# micro.net
KiCad netlist of a schematic drawn in Altium Designer
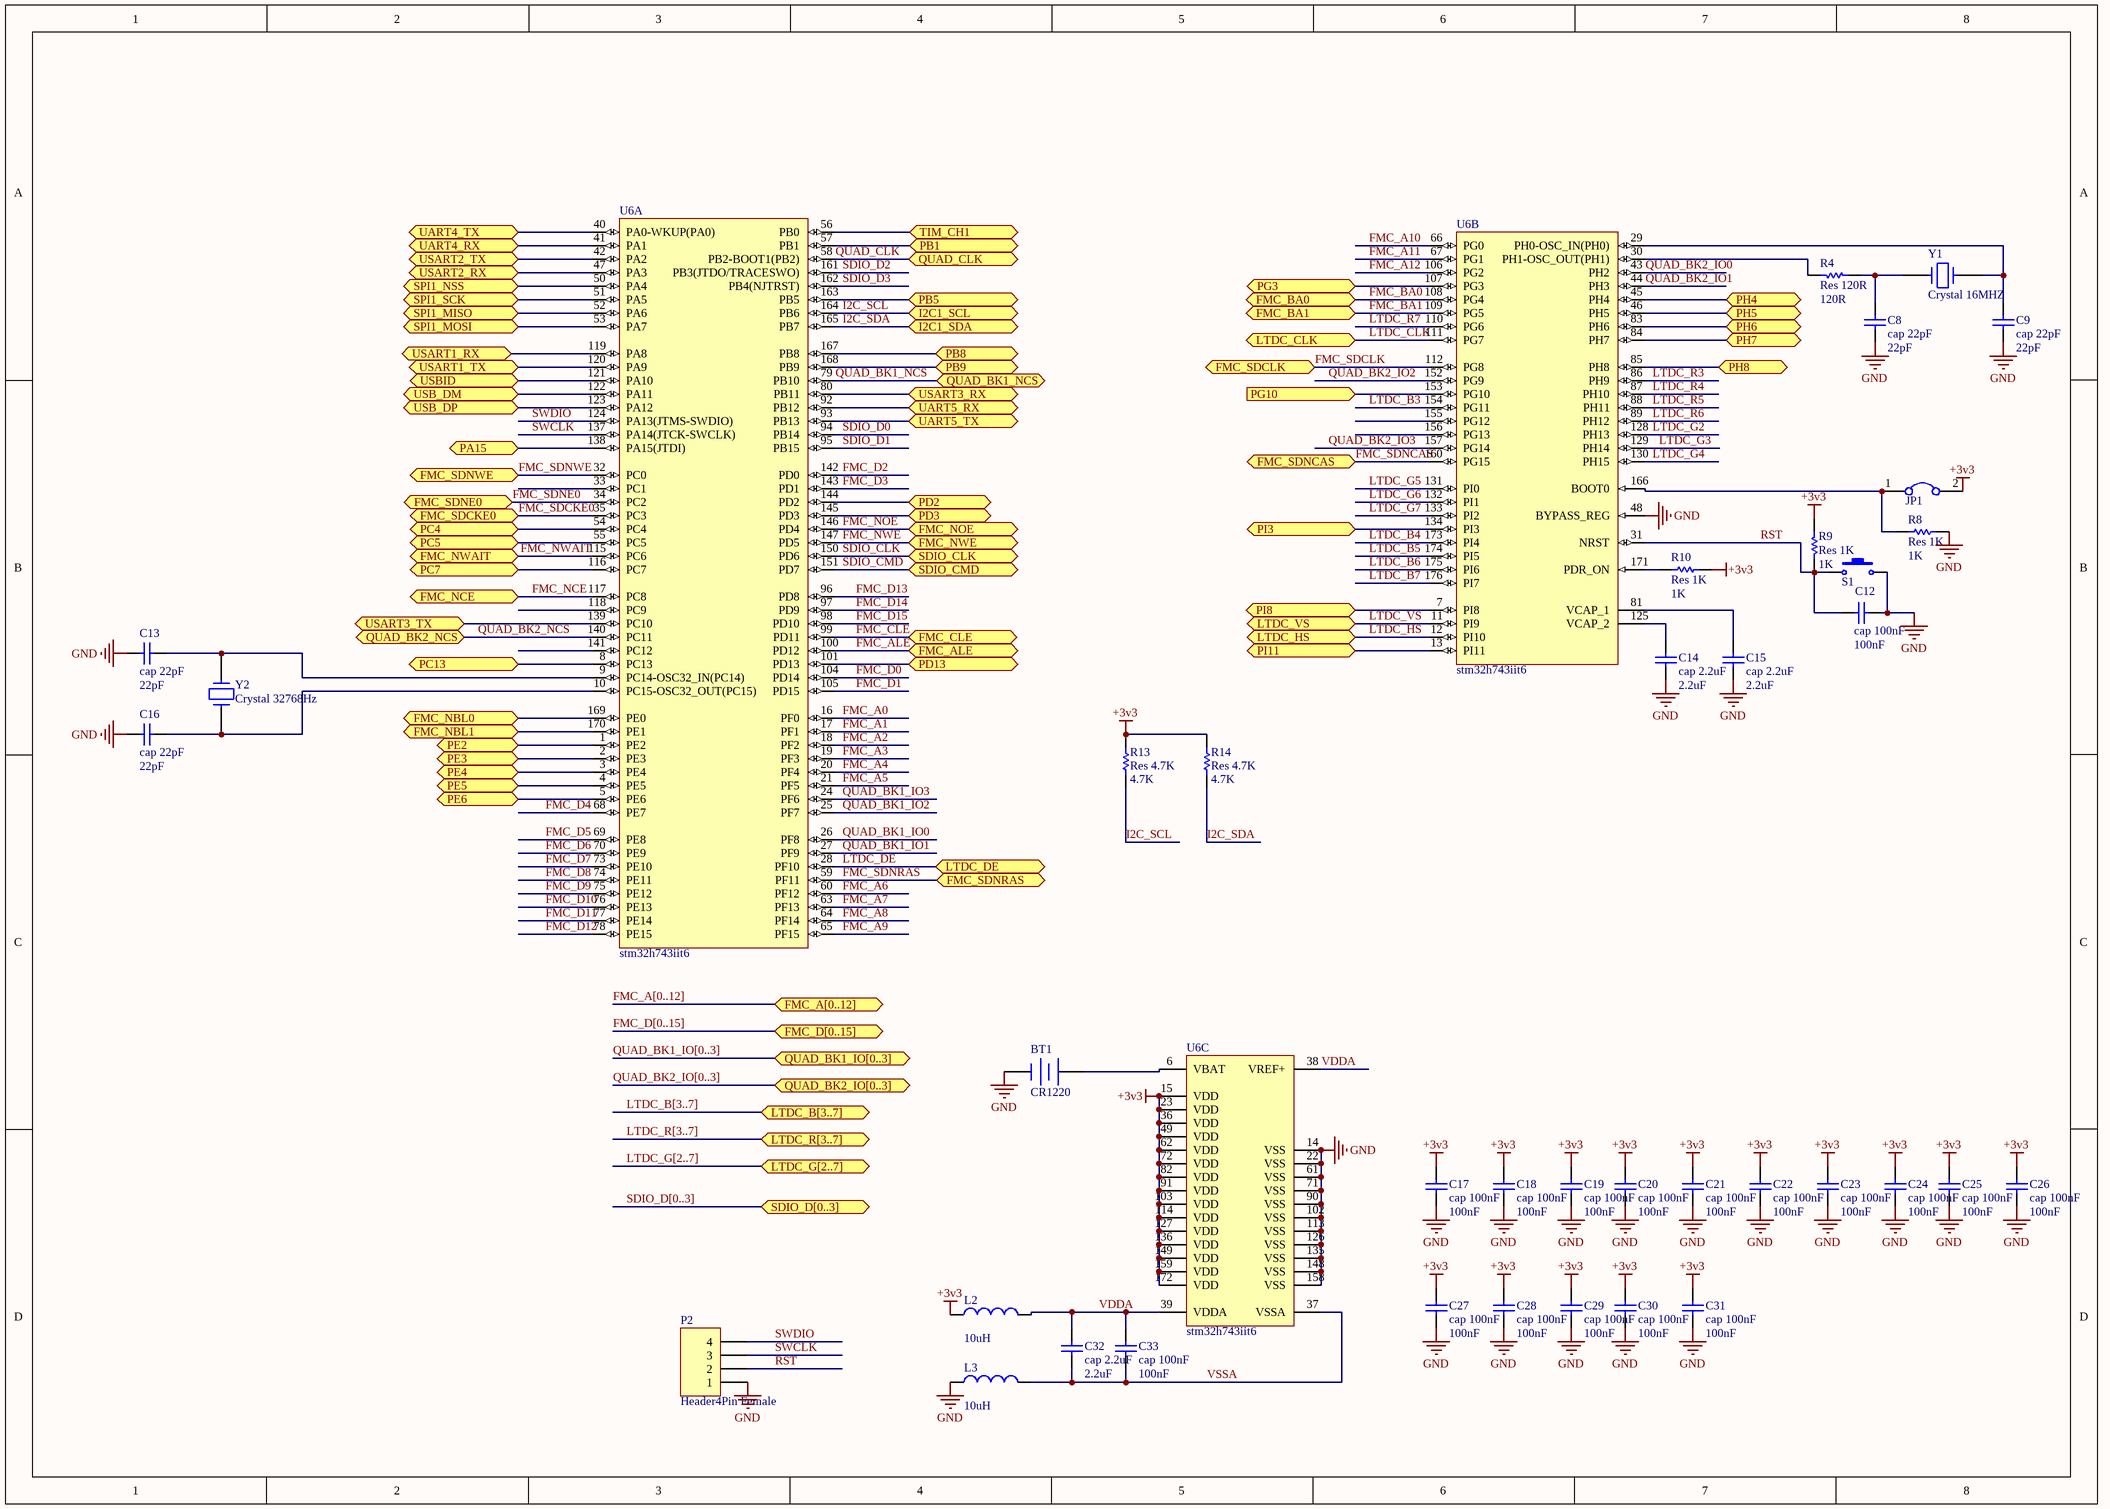
[diagram p0: micro.SchDoc]

(export (version "E")
  (design (tool "Eeschema 10.0.6"))
  (components
    (comp (ref "BT1")
      (value "CR1220")
      (footprint "BTH1220")
      (description "CoinCell Battery")
      (fields (field (name "PUBLISHER") "Altium Limited"))
      (libsource (lib "Miscellaneous Devices") (part "Battery"))
    )
    (comp (ref "C8")
      (value "cap 22pF")
      (footprint "Cap 805")
      (description "Capacitor")
      (fields (field (name "ALTIUM_VALUE") "22pF") (field (name "PUBLISHER") "Altium Limited"))
      (libsource (lib "Miscellaneous Devices") (part "Cap"))
    )
    (comp (ref "C9")
      (value "cap 22pF")
      (footprint "Cap 805")
      (description "Capacitor")
      (fields (field (name "ALTIUM_VALUE") "22pF") (field (name "PUBLISHER") "Altium Limited"))
      (libsource (lib "Miscellaneous Devices") (part "Cap"))
    )
    (comp (ref "C12")
      (value "cap 100nF")
      (footprint "Cap 805")
      (description "Capacitor")
      (fields (field (name "ALTIUM_VALUE") "100nF") (field (name "PUBLISHER") "Altium Limited"))
      (libsource (lib "Miscellaneous Devices") (part "Cap"))
    )
    (comp (ref "C13")
      (value "cap 22pF")
      (footprint "Cap 805")
      (description "Capacitor")
      (fields (field (name "ALTIUM_VALUE") "22pF") (field (name "PUBLISHER") "Altium Limited"))
      (libsource (lib "Miscellaneous Devices") (part "Cap"))
    )
    (comp (ref "C14")
      (value "cap 2.2uF")
      (footprint "Cap 805")
      (description "Capacitor")
      (fields (field (name "ALTIUM_VALUE") "2.2uF") (field (name "PUBLISHER") "Altium Limited"))
      (libsource (lib "Miscellaneous Devices") (part "Cap"))
    )
    (comp (ref "C15")
      (value "cap 2.2uF")
      (footprint "Cap 805")
      (description "Capacitor")
      (fields (field (name "ALTIUM_VALUE") "2.2uF") (field (name "PUBLISHER") "Altium Limited"))
      (libsource (lib "Miscellaneous Devices") (part "Cap"))
    )
    (comp (ref "C16")
      (value "cap 22pF")
      (footprint "Cap 805")
      (description "Capacitor")
      (fields (field (name "ALTIUM_VALUE") "22pF") (field (name "PUBLISHER") "Altium Limited"))
      (libsource (lib "Miscellaneous Devices") (part "Cap"))
    )
    (comp (ref "C17")
      (value "cap 100nF")
      (footprint "Cap 805")
      (description "Capacitor")
      (fields (field (name "ALTIUM_VALUE") "100nF") (field (name "PUBLISHER") "Altium Limited"))
      (libsource (lib "Miscellaneous Devices") (part "Cap"))
    )
    (comp (ref "C18")
      (value "cap 100nF")
      (footprint "Cap 805")
      (description "Capacitor")
      (fields (field (name "ALTIUM_VALUE") "100nF") (field (name "PUBLISHER") "Altium Limited"))
      (libsource (lib "Miscellaneous Devices") (part "Cap"))
    )
    (comp (ref "C19")
      (value "cap 100nF")
      (footprint "Cap 805")
      (description "Capacitor")
      (fields (field (name "ALTIUM_VALUE") "100nF") (field (name "PUBLISHER") "Altium Limited"))
      (libsource (lib "Miscellaneous Devices") (part "Cap"))
    )
    (comp (ref "C20")
      (value "cap 100nF")
      (footprint "Cap 805")
      (description "Capacitor")
      (fields (field (name "ALTIUM_VALUE") "100nF") (field (name "PUBLISHER") "Altium Limited"))
      (libsource (lib "Miscellaneous Devices") (part "Cap"))
    )
    (comp (ref "C21")
      (value "cap 100nF")
      (footprint "Cap 805")
      (description "Capacitor")
      (fields (field (name "ALTIUM_VALUE") "100nF") (field (name "PUBLISHER") "Altium Limited"))
      (libsource (lib "Miscellaneous Devices") (part "Cap"))
    )
    (comp (ref "C22")
      (value "cap 100nF")
      (footprint "Cap 805")
      (description "Capacitor")
      (fields (field (name "ALTIUM_VALUE") "100nF") (field (name "PUBLISHER") "Altium Limited"))
      (libsource (lib "Miscellaneous Devices") (part "Cap"))
    )
    (comp (ref "C23")
      (value "cap 100nF")
      (footprint "Cap 805")
      (description "Capacitor")
      (fields (field (name "ALTIUM_VALUE") "100nF") (field (name "PUBLISHER") "Altium Limited"))
      (libsource (lib "Miscellaneous Devices") (part "Cap"))
    )
    (comp (ref "C24")
      (value "cap 100nF")
      (footprint "Cap 805")
      (description "Capacitor")
      (fields (field (name "ALTIUM_VALUE") "100nF") (field (name "PUBLISHER") "Altium Limited"))
      (libsource (lib "Miscellaneous Devices") (part "Cap"))
    )
    (comp (ref "C25")
      (value "cap 100nF")
      (footprint "Cap 805")
      (description "Capacitor")
      (fields (field (name "ALTIUM_VALUE") "100nF") (field (name "PUBLISHER") "Altium Limited"))
      (libsource (lib "Miscellaneous Devices") (part "Cap"))
    )
    (comp (ref "C26")
      (value "cap 100nF")
      (footprint "Cap 805")
      (description "Capacitor")
      (fields (field (name "ALTIUM_VALUE") "100nF") (field (name "PUBLISHER") "Altium Limited"))
      (libsource (lib "Miscellaneous Devices") (part "Cap"))
    )
    (comp (ref "C27")
      (value "cap 100nF")
      (footprint "Cap 805")
      (description "Capacitor")
      (fields (field (name "ALTIUM_VALUE") "100nF") (field (name "PUBLISHER") "Altium Limited"))
      (libsource (lib "Miscellaneous Devices") (part "Cap"))
    )
    (comp (ref "C28")
      (value "cap 100nF")
      (footprint "Cap 805")
      (description "Capacitor")
      (fields (field (name "ALTIUM_VALUE") "100nF") (field (name "PUBLISHER") "Altium Limited"))
      (libsource (lib "Miscellaneous Devices") (part "Cap"))
    )
    (comp (ref "C29")
      (value "cap 100nF")
      (footprint "Cap 805")
      (description "Capacitor")
      (fields (field (name "ALTIUM_VALUE") "100nF") (field (name "PUBLISHER") "Altium Limited"))
      (libsource (lib "Miscellaneous Devices") (part "Cap"))
    )
    (comp (ref "C30")
      (value "cap 100nF")
      (footprint "Cap 805")
      (description "Capacitor")
      (fields (field (name "ALTIUM_VALUE") "100nF") (field (name "PUBLISHER") "Altium Limited"))
      (libsource (lib "Miscellaneous Devices") (part "Cap"))
    )
    (comp (ref "C31")
      (value "cap 100nF")
      (footprint "Cap 805")
      (description "Capacitor")
      (fields (field (name "ALTIUM_VALUE") "100nF") (field (name "PUBLISHER") "Altium Limited"))
      (libsource (lib "Miscellaneous Devices") (part "Cap"))
    )
    (comp (ref "C32")
      (value "cap 2.2uF")
      (footprint "Cap 805")
      (description "Capacitor")
      (fields (field (name "ALTIUM_VALUE") "2.2uF") (field (name "PUBLISHER") "Altium Limited"))
      (libsource (lib "Miscellaneous Devices") (part "Cap"))
    )
    (comp (ref "C33")
      (value "cap 100nF")
      (footprint "Cap 805")
      (description "Capacitor")
      (fields (field (name "ALTIUM_VALUE") "100nF") (field (name "PUBLISHER") "Altium Limited"))
      (libsource (lib "Miscellaneous Devices") (part "Cap"))
    )
    (comp (ref "JP1")
      (value "Jumper")
      (footprint "Jumper Small - 2.54 - GRAY")
      (description "Boot select")
      (libsource (lib "Altium (2)") (part "Jumper"))
    )
    (comp (ref "L2")
      (value "10uH")
      (footprint "IND1206")
      (description "Inductor")
      (fields (field (name "Comment") "inductor 10uH") (field (name "PUBLISHER") "Altium Limited"))
      (libsource (lib "Miscellaneous Devices") (part "Inductor"))
    )
    (comp (ref "L3")
      (value "10uH")
      (footprint "IND1206")
      (description "Inductor")
      (fields (field (name "Comment") "inductor 10uH") (field (name "PUBLISHER") "Altium Limited"))
      (libsource (lib "Miscellaneous Devices") (part "Inductor"))
    )
    (comp (ref "P2")
      (value "Header4Pin Female")
      (footprint "HDR1X4")
      (description "Header, 4-Pin")
      (fields (field (name "PUBLISHER") "Altium Limited"))
      (libsource (lib "Miscellaneous Connectors") (part "Header 4"))
    )
    (comp (ref "R4")
      (value "Res 120R")
      (footprint "RES 0805 (2012X06L)")
      (description "Resistor")
      (fields (field (name "ALTIUM_VALUE") "120R") (field (name "PUBLISHER") "Altium Limited"))
      (libsource (lib "Miscellaneous Devices") (part "Res1"))
    )
    (comp (ref "R8")
      (value "Res 1K")
      (footprint "RES 0805 (2012X06L)")
      (description "Resistor")
      (fields (field (name "ALTIUM_VALUE") "1K") (field (name "PUBLISHER") "Altium Limited"))
      (libsource (lib "Miscellaneous Devices") (part "Res1"))
    )
    (comp (ref "R9")
      (value "Res 1K")
      (footprint "RES 0805 (2012X06L)")
      (description "Resistor")
      (fields (field (name "ALTIUM_VALUE") "1K") (field (name "PUBLISHER") "Altium Limited"))
      (libsource (lib "Miscellaneous Devices") (part "Res1"))
    )
    (comp (ref "R10")
      (value "Res 1K")
      (footprint "RES 0805 (2012X06L)")
      (description "Resistor")
      (fields (field (name "ALTIUM_VALUE") "1K") (field (name "PUBLISHER") "Altium Limited"))
      (libsource (lib "Miscellaneous Devices") (part "Res1"))
    )
    (comp (ref "R13")
      (value "Res 4.7K")
      (footprint "RES 0805 (2012X06L)")
      (description "Resistor")
      (fields (field (name "ALTIUM_VALUE") "4.7K") (field (name "PUBLISHER") "Altium Limited"))
      (libsource (lib "Miscellaneous Devices") (part "Res1"))
    )
    (comp (ref "R14")
      (value "Res 4.7K")
      (footprint "RES 0805 (2012X06L)")
      (description "Resistor")
      (fields (field (name "ALTIUM_VALUE") "4.7K") (field (name "PUBLISHER") "Altium Limited"))
      (libsource (lib "Miscellaneous Devices") (part "Res1"))
    )
    (comp (ref "S1")
      (value "Switch PB")
      (footprint "Switch - Push to On")
      (description "Push Button Switch")
      (libsource (lib "Altium (2)") (part "Switch PB"))
    )
    (comp (ref "U6")
      (value "stm32h743iit6")
      (footprint "STM-LQFP176_M")
      (fields (field (name "MANUFACTURER") "STMicroelectronics") (field (name "PARTNUMBER") "STM32F429IGT6"))
      (libsource (lib "STMicroelectronics STM32 F4") (part "STM32F429IGT6"))
    )
    (comp (ref "Y1")
      (value "Crystal 16MHZ")
      (footprint "CRYSTAL Small")
      (description "Crystal")
      (libsource (lib "Altium library (www.AVRelec.com)") (part "CRYSTAL"))
    )
    (comp (ref "Y2")
      (value "Crystal 32768Hz")
      (footprint "XTAL RTC")
      (description "Crystal")
      (libsource (lib "Altium library (www.AVRelec.com)") (part "CRYSTAL"))
    )
  )
  (nets
    (net (code "1") (name "+3v3") (class "Default")
      (node (ref "C17") (pin "2") (pinfunction "2_2") (pintype "passive"))
      (node (ref "C18") (pin "2") (pinfunction "2_2") (pintype "passive"))
      (node (ref "C19") (pin "2") (pinfunction "2_2") (pintype "passive"))
      (node (ref "C20") (pin "2") (pinfunction "2_2") (pintype "passive"))
      (node (ref "C21") (pin "2") (pinfunction "2_2") (pintype "passive"))
      (node (ref "C22") (pin "2") (pinfunction "2_2") (pintype "passive"))
      (node (ref "C23") (pin "2") (pinfunction "2_2") (pintype "passive"))
      (node (ref "C24") (pin "2") (pinfunction "2_2") (pintype "passive"))
      (node (ref "C25") (pin "2") (pinfunction "2_2") (pintype "passive"))
      (node (ref "C26") (pin "2") (pinfunction "2_2") (pintype "passive"))
      (node (ref "C27") (pin "2") (pinfunction "2_2") (pintype "passive"))
      (node (ref "C28") (pin "2") (pinfunction "2_2") (pintype "passive"))
      (node (ref "C29") (pin "2") (pinfunction "2_2") (pintype "passive"))
      (node (ref "C30") (pin "2") (pinfunction "2_2") (pintype "passive"))
      (node (ref "C31") (pin "2") (pinfunction "2_2") (pintype "passive"))
      (node (ref "JP1") (pin "2") (pinfunction "2_2") (pintype "passive"))
      (node (ref "L2") (pin "1") (pinfunction "1_1") (pintype "passive"))
      (node (ref "R10") (pin "2") (pinfunction "2_2") (pintype "passive"))
      (node (ref "R13") (pin "1") (pinfunction "1_1") (pintype "passive"))
      (node (ref "R14") (pin "1") (pinfunction "1_1") (pintype "passive"))
      (node (ref "R9") (pin "1") (pinfunction "1_1") (pintype "passive"))
      (node (ref "U6") (pin "103") (pinfunction "VDD_103") (pintype "power_in"))
      (node (ref "U6") (pin "114") (pinfunction "VDD_114") (pintype "power_in"))
      (node (ref "U6") (pin "127") (pinfunction "VDD_127") (pintype "power_in"))
      (node (ref "U6") (pin "136") (pinfunction "VDD_136") (pintype "power_in"))
      (node (ref "U6") (pin "149") (pinfunction "VDD_149") (pintype "power_in"))
      (node (ref "U6") (pin "15") (pinfunction "VDD_15") (pintype "power_in"))
      (node (ref "U6") (pin "159") (pinfunction "VDD_159") (pintype "power_in"))
      (node (ref "U6") (pin "172") (pinfunction "VDD_172") (pintype "power_in"))
      (node (ref "U6") (pin "23") (pinfunction "VDD_23") (pintype "power_in"))
      (node (ref "U6") (pin "36") (pinfunction "VDD_36") (pintype "power_in"))
      (node (ref "U6") (pin "49") (pinfunction "VDD_49") (pintype "power_in"))
      (node (ref "U6") (pin "62") (pinfunction "VDD_62") (pintype "power_in"))
      (node (ref "U6") (pin "72") (pinfunction "VDD_72") (pintype "power_in"))
      (node (ref "U6") (pin "82") (pinfunction "VDD_82") (pintype "power_in"))
      (node (ref "U6") (pin "91") (pinfunction "VDD_91") (pintype "power_in"))
    )
    (net (code "2") (name "/FMC_A0") (class "Default")
      (node (ref "U6") (pin "16") (pinfunction "PF0_16") (pintype "bidirectional"))
    )
    (net (code "3") (name "/FMC_A1") (class "Default")
      (node (ref "U6") (pin "17") (pinfunction "PF1_17") (pintype "bidirectional"))
    )
    (net (code "4") (name "/FMC_A2") (class "Default")
      (node (ref "U6") (pin "18") (pinfunction "PF2_18") (pintype "bidirectional"))
    )
    (net (code "5") (name "/FMC_A3") (class "Default")
      (node (ref "U6") (pin "19") (pinfunction "PF3_19") (pintype "bidirectional"))
    )
    (net (code "6") (name "/FMC_A4") (class "Default")
      (node (ref "U6") (pin "20") (pinfunction "PF4_20") (pintype "bidirectional"))
    )
    (net (code "7") (name "/FMC_A5") (class "Default")
      (node (ref "U6") (pin "21") (pinfunction "PF5_21") (pintype "bidirectional"))
    )
    (net (code "8") (name "/FMC_A6") (class "Default")
      (node (ref "U6") (pin "60") (pinfunction "PF12_60") (pintype "bidirectional"))
    )
    (net (code "9") (name "/FMC_A7") (class "Default")
      (node (ref "U6") (pin "63") (pinfunction "PF13_63") (pintype "bidirectional"))
    )
    (net (code "10") (name "/FMC_A8") (class "Default")
      (node (ref "U6") (pin "64") (pinfunction "PF14_64") (pintype "bidirectional"))
    )
    (net (code "11") (name "/FMC_A9") (class "Default")
      (node (ref "U6") (pin "65") (pinfunction "PF15_65") (pintype "bidirectional"))
    )
    (net (code "12") (name "/FMC_A10") (class "Default")
      (node (ref "U6") (pin "66") (pinfunction "PG0_66") (pintype "bidirectional"))
    )
    (net (code "13") (name "/FMC_A11") (class "Default")
      (node (ref "U6") (pin "67") (pinfunction "PG1_67") (pintype "bidirectional"))
    )
    (net (code "14") (name "/FMC_A12") (class "Default")
      (node (ref "U6") (pin "106") (pinfunction "PG2_106") (pintype "bidirectional"))
    )
    (net (code "15") (name "/FMC_ALE") (class "Default")
      (node (ref "U6") (pin "100") (pinfunction "PD12_100") (pintype "bidirectional"))
    )
    (net (code "17") (name "/FMC_BA0") (class "Default")
      (node (ref "U6") (pin "108") (pinfunction "PG4_108") (pintype "bidirectional"))
    )
    (net (code "18") (name "/FMC_BA1") (class "Default")
      (node (ref "U6") (pin "109") (pinfunction "PG5_109") (pintype "bidirectional"))
    )
    (net (code "19") (name "/FMC_CLE") (class "Default")
      (node (ref "U6") (pin "99") (pinfunction "PD11_99") (pintype "bidirectional"))
    )
    (net (code "20") (name "/FMC_D0") (class "Default")
      (node (ref "U6") (pin "104") (pinfunction "PD14_104") (pintype "bidirectional"))
    )
    (net (code "21") (name "/FMC_D1") (class "Default")
      (node (ref "U6") (pin "105") (pinfunction "PD15_105") (pintype "bidirectional"))
    )
    (net (code "22") (name "/FMC_D2") (class "Default")
      (node (ref "U6") (pin "142") (pinfunction "PD0_142") (pintype "bidirectional"))
    )
    (net (code "23") (name "/FMC_D3") (class "Default")
      (node (ref "U6") (pin "143") (pinfunction "PD1_143") (pintype "bidirectional"))
    )
    (net (code "24") (name "/FMC_D4") (class "Default")
      (node (ref "U6") (pin "68") (pinfunction "PE7_68") (pintype "bidirectional"))
    )
    (net (code "25") (name "/FMC_D5") (class "Default")
      (node (ref "U6") (pin "69") (pinfunction "PE8_69") (pintype "bidirectional"))
    )
    (net (code "26") (name "/FMC_D6") (class "Default")
      (node (ref "U6") (pin "70") (pinfunction "PE9_70") (pintype "bidirectional"))
    )
    (net (code "27") (name "/FMC_D7") (class "Default")
      (node (ref "U6") (pin "73") (pinfunction "PE10_73") (pintype "bidirectional"))
    )
    (net (code "28") (name "/FMC_D8") (class "Default")
      (node (ref "U6") (pin "74") (pinfunction "PE11_74") (pintype "bidirectional"))
    )
    (net (code "29") (name "/FMC_D9") (class "Default")
      (node (ref "U6") (pin "75") (pinfunction "PE12_75") (pintype "bidirectional"))
    )
    (net (code "30") (name "/FMC_D10") (class "Default")
      (node (ref "U6") (pin "76") (pinfunction "PE13_76") (pintype "bidirectional"))
    )
    (net (code "31") (name "/FMC_D11") (class "Default")
      (node (ref "U6") (pin "77") (pinfunction "PE14_77") (pintype "bidirectional"))
    )
    (net (code "32") (name "/FMC_D12") (class "Default")
      (node (ref "U6") (pin "78") (pinfunction "PE15_78") (pintype "bidirectional"))
    )
    (net (code "33") (name "/FMC_D13") (class "Default")
      (node (ref "U6") (pin "96") (pinfunction "PD8_96") (pintype "bidirectional"))
    )
    (net (code "34") (name "/FMC_D14") (class "Default")
      (node (ref "U6") (pin "97") (pinfunction "PD9_97") (pintype "bidirectional"))
    )
    (net (code "35") (name "/FMC_D15") (class "Default")
      (node (ref "U6") (pin "98") (pinfunction "PD10_98") (pintype "bidirectional"))
    )
    (net (code "37") (name "/FMC_NBL0") (class "Default")
      (node (ref "U6") (pin "169") (pinfunction "PE0_169") (pintype "bidirectional"))
    )
    (net (code "38") (name "/FMC_NBL1") (class "Default")
      (node (ref "U6") (pin "170") (pinfunction "PE1_170") (pintype "bidirectional"))
    )
    (net (code "39") (name "/FMC_NCE") (class "Default")
      (node (ref "U6") (pin "117") (pinfunction "PC8_117") (pintype "bidirectional"))
    )
    (net (code "40") (name "/FMC_NOE") (class "Default")
      (node (ref "U6") (pin "146") (pinfunction "PD4_146") (pintype "bidirectional"))
    )
    (net (code "41") (name "/FMC_NWAIT") (class "Default")
      (node (ref "U6") (pin "115") (pinfunction "PC6_115") (pintype "bidirectional"))
    )
    (net (code "42") (name "/FMC_NWE") (class "Default")
      (node (ref "U6") (pin "147") (pinfunction "PD5_147") (pintype "bidirectional"))
    )
    (net (code "43") (name "/FMC_SDCKE0") (class "Default")
      (node (ref "U6") (pin "35") (pinfunction "PC3_35") (pintype "bidirectional"))
    )
    (net (code "44") (name "/FMC_SDCLK") (class "Default")
      (node (ref "U6") (pin "112") (pinfunction "PG8_112") (pintype "bidirectional"))
    )
    (net (code "45") (name "/FMC_SDNCAS") (class "Default")
      (node (ref "U6") (pin "160") (pinfunction "PG15_160") (pintype "bidirectional"))
    )
    (net (code "46") (name "/FMC_SDNE0") (class "Default")
      (node (ref "U6") (pin "34") (pinfunction "PC2_34") (pintype "bidirectional"))
    )
    (net (code "47") (name "/FMC_SDNRAS") (class "Default")
      (node (ref "U6") (pin "59") (pinfunction "PF11_59") (pintype "bidirectional"))
    )
    (net (code "48") (name "/FMC_SDNWE") (class "Default")
      (node (ref "U6") (pin "32") (pinfunction "PC0_32") (pintype "bidirectional"))
    )
    (net (code "49") (name "/I2C_SCL") (class "Default")
      (node (ref "R13") (pin "2") (pinfunction "2_2") (pintype "passive"))
      (node (ref "U6") (pin "164") (pinfunction "PB6_164") (pintype "bidirectional"))
    )
    (net (code "50") (name "/I2C_SDA") (class "Default")
      (node (ref "R14") (pin "2") (pinfunction "2_2") (pintype "passive"))
      (node (ref "U6") (pin "165") (pinfunction "PB7_165") (pintype "bidirectional"))
    )
    (net (code "51") (name "/LTDC_B3") (class "Default")
      (node (ref "U6") (pin "154") (pinfunction "PG11_154") (pintype "bidirectional"))
    )
    (net (code "52") (name "/LTDC_B4") (class "Default")
      (node (ref "U6") (pin "173") (pinfunction "PI4_173") (pintype "bidirectional"))
    )
    (net (code "53") (name "/LTDC_B5") (class "Default")
      (node (ref "U6") (pin "174") (pinfunction "PI5_174") (pintype "bidirectional"))
    )
    (net (code "54") (name "/LTDC_B6") (class "Default")
      (node (ref "U6") (pin "175") (pinfunction "PI6_175") (pintype "bidirectional"))
    )
    (net (code "55") (name "/LTDC_B7") (class "Default")
      (node (ref "U6") (pin "176") (pinfunction "PI7_176") (pintype "bidirectional"))
    )
    (net (code "57") (name "/LTDC_CLK") (class "Default")
      (node (ref "U6") (pin "111") (pinfunction "PG7_111") (pintype "bidirectional"))
    )
    (net (code "58") (name "/LTDC_DE") (class "Default")
      (node (ref "U6") (pin "28") (pinfunction "PF10_28") (pintype "bidirectional"))
    )
    (net (code "59") (name "/LTDC_G2") (class "Default")
      (node (ref "U6") (pin "128") (pinfunction "PH13_128") (pintype "bidirectional"))
    )
    (net (code "60") (name "/LTDC_G3") (class "Default")
      (node (ref "U6") (pin "129") (pinfunction "PH14_129") (pintype "bidirectional"))
    )
    (net (code "61") (name "/LTDC_G4") (class "Default")
      (node (ref "U6") (pin "130") (pinfunction "PH15_130") (pintype "bidirectional"))
    )
    (net (code "62") (name "/LTDC_G5") (class "Default")
      (node (ref "U6") (pin "131") (pinfunction "PI0_131") (pintype "bidirectional"))
    )
    (net (code "63") (name "/LTDC_G6") (class "Default")
      (node (ref "U6") (pin "132") (pinfunction "PI1_132") (pintype "bidirectional"))
    )
    (net (code "64") (name "/LTDC_G7") (class "Default")
      (node (ref "U6") (pin "133") (pinfunction "PI2_133") (pintype "bidirectional"))
    )
    (net (code "66") (name "/LTDC_HS") (class "Default")
      (node (ref "U6") (pin "12") (pinfunction "PI10_12") (pintype "bidirectional"))
    )
    (net (code "67") (name "/LTDC_R3") (class "Default")
      (node (ref "U6") (pin "86") (pinfunction "PH9_86") (pintype "bidirectional"))
    )
    (net (code "68") (name "/LTDC_R4") (class "Default")
      (node (ref "U6") (pin "87") (pinfunction "PH10_87") (pintype "bidirectional"))
    )
    (net (code "69") (name "/LTDC_R5") (class "Default")
      (node (ref "U6") (pin "88") (pinfunction "PH11_88") (pintype "bidirectional"))
    )
    (net (code "70") (name "/LTDC_R6") (class "Default")
      (node (ref "U6") (pin "89") (pinfunction "PH12_89") (pintype "bidirectional"))
    )
    (net (code "71") (name "/LTDC_R7") (class "Default")
      (node (ref "U6") (pin "110") (pinfunction "PG6_110") (pintype "bidirectional"))
    )
    (net (code "73") (name "/LTDC_VS") (class "Default")
      (node (ref "U6") (pin "11") (pinfunction "PI9_11") (pintype "bidirectional"))
    )
    (net (code "74") (name "/PA15") (class "Default")
      (node (ref "U6") (pin "138") (pinfunction "PA15(JTDI)_138") (pintype "bidirectional"))
    )
    (net (code "75") (name "/PB1") (class "Default")
      (node (ref "U6") (pin "57") (pinfunction "PB1_57") (pintype "bidirectional"))
    )
    (net (code "76") (name "/PB5") (class "Default")
      (node (ref "U6") (pin "163") (pinfunction "PB5_163") (pintype "bidirectional"))
    )
    (net (code "77") (name "/PB8") (class "Default")
      (node (ref "U6") (pin "167") (pinfunction "PB8_167") (pintype "bidirectional"))
    )
    (net (code "78") (name "/PB9") (class "Default")
      (node (ref "U6") (pin "168") (pinfunction "PB9_168") (pintype "bidirectional"))
    )
    (net (code "79") (name "/PC4") (class "Default")
      (node (ref "U6") (pin "54") (pinfunction "PC4_54") (pintype "bidirectional"))
    )
    (net (code "80") (name "/PC5") (class "Default")
      (node (ref "U6") (pin "55") (pinfunction "PC5_55") (pintype "bidirectional"))
    )
    (net (code "81") (name "/PC7") (class "Default")
      (node (ref "U6") (pin "116") (pinfunction "PC7_116") (pintype "bidirectional"))
    )
    (net (code "82") (name "/PC13") (class "Default")
      (node (ref "U6") (pin "8") (pinfunction "PC13_8") (pintype "bidirectional"))
    )
    (net (code "83") (name "/PD2") (class "Default")
      (node (ref "U6") (pin "144") (pinfunction "PD2_144") (pintype "bidirectional"))
    )
    (net (code "84") (name "/PD3") (class "Default")
      (node (ref "U6") (pin "145") (pinfunction "PD3_145") (pintype "bidirectional"))
    )
    (net (code "85") (name "/PD13") (class "Default")
      (node (ref "U6") (pin "101") (pinfunction "PD13_101") (pintype "bidirectional"))
    )
    (net (code "86") (name "/PE2") (class "Default")
      (node (ref "U6") (pin "1") (pinfunction "PE2_1") (pintype "bidirectional"))
    )
    (net (code "87") (name "/PE3") (class "Default")
      (node (ref "U6") (pin "2") (pinfunction "PE3_2") (pintype "bidirectional"))
    )
    (net (code "88") (name "/PE4") (class "Default")
      (node (ref "U6") (pin "3") (pinfunction "PE4_3") (pintype "bidirectional"))
    )
    (net (code "89") (name "/PE5") (class "Default")
      (node (ref "U6") (pin "4") (pinfunction "PE5_4") (pintype "bidirectional"))
    )
    (net (code "90") (name "/PE6") (class "Default")
      (node (ref "U6") (pin "5") (pinfunction "PE6_5") (pintype "bidirectional"))
    )
    (net (code "91") (name "/PG3") (class "Default")
      (node (ref "U6") (pin "107") (pinfunction "PG3_107") (pintype "bidirectional"))
    )
    (net (code "92") (name "/PG10") (class "Default")
      (node (ref "U6") (pin "153") (pinfunction "PG10_153") (pintype "bidirectional"))
    )
    (net (code "93") (name "/PH4") (class "Default")
      (node (ref "U6") (pin "45") (pinfunction "PH4_45") (pintype "bidirectional"))
    )
    (net (code "94") (name "/PH5") (class "Default")
      (node (ref "U6") (pin "46") (pinfunction "PH5_46") (pintype "bidirectional"))
    )
    (net (code "95") (name "/PH6") (class "Default")
      (node (ref "U6") (pin "83") (pinfunction "PH6_83") (pintype "bidirectional"))
    )
    (net (code "96") (name "/PH7") (class "Default")
      (node (ref "U6") (pin "84") (pinfunction "PH7_84") (pintype "bidirectional"))
    )
    (net (code "97") (name "/PH8") (class "Default")
      (node (ref "U6") (pin "85") (pinfunction "PH8_85") (pintype "bidirectional"))
    )
    (net (code "98") (name "/PI3") (class "Default")
      (node (ref "U6") (pin "134") (pinfunction "PI3_134") (pintype "bidirectional"))
    )
    (net (code "99") (name "/PI8") (class "Default")
      (node (ref "U6") (pin "7") (pinfunction "PI8_7") (pintype "bidirectional"))
    )
    (net (code "100") (name "/PI11") (class "Default")
      (node (ref "U6") (pin "13") (pinfunction "PI11_13") (pintype "bidirectional"))
    )
    (net (code "101") (name "/QUAD_BK1_IO0") (class "Default")
      (node (ref "U6") (pin "26") (pinfunction "PF8_26") (pintype "bidirectional"))
    )
    (net (code "102") (name "/QUAD_BK1_IO1") (class "Default")
      (node (ref "U6") (pin "27") (pinfunction "PF9_27") (pintype "bidirectional"))
    )
    (net (code "103") (name "/QUAD_BK1_IO2") (class "Default")
      (node (ref "U6") (pin "25") (pinfunction "PF7_25") (pintype "bidirectional"))
    )
    (net (code "104") (name "/QUAD_BK1_IO3") (class "Default")
      (node (ref "U6") (pin "24") (pinfunction "PF6_24") (pintype "bidirectional"))
    )
    (net (code "106") (name "/QUAD_BK1_NCS") (class "Default")
      (node (ref "U6") (pin "79") (pinfunction "PB10_79") (pintype "bidirectional"))
    )
    (net (code "107") (name "/QUAD_BK2_IO0") (class "Default")
      (node (ref "U6") (pin "43") (pinfunction "PH2_43") (pintype "bidirectional"))
    )
    (net (code "108") (name "/QUAD_BK2_IO1") (class "Default")
      (node (ref "U6") (pin "44") (pinfunction "PH3_44") (pintype "bidirectional"))
    )
    (net (code "109") (name "/QUAD_BK2_IO2") (class "Default")
      (node (ref "U6") (pin "152") (pinfunction "PG9_152") (pintype "bidirectional"))
    )
    (net (code "110") (name "/QUAD_BK2_IO3") (class "Default")
      (node (ref "U6") (pin "157") (pinfunction "PG14_157") (pintype "bidirectional"))
    )
    (net (code "112") (name "/QUAD_BK2_NCS") (class "Default")
      (node (ref "U6") (pin "140") (pinfunction "PC11_140") (pintype "bidirectional"))
    )
    (net (code "113") (name "/QUAD_CLK") (class "Default")
      (node (ref "U6") (pin "58") (pinfunction "PB2-BOOT1(PB2)_58") (pintype "bidirectional"))
    )
    (net (code "114") (name "/RST") (class "Default")
      (node (ref "C12") (pin "1") (pinfunction "1_1") (pintype "passive"))
      (node (ref "P2") (pin "2") (pinfunction "2_2") (pintype "passive"))
      (node (ref "R9") (pin "2") (pinfunction "2_2") (pintype "passive"))
      (node (ref "S1") (pin "2") (pinfunction "2_2") (pintype "passive"))
      (node (ref "U6") (pin "31") (pinfunction "NRST_31") (pintype "bidirectional"))
    )
    (net (code "115") (name "/SDIO_CLK") (class "Default")
      (node (ref "U6") (pin "150") (pinfunction "PD6_150") (pintype "bidirectional"))
    )
    (net (code "116") (name "/SDIO_CMD") (class "Default")
      (node (ref "U6") (pin "151") (pinfunction "PD7_151") (pintype "bidirectional"))
    )
    (net (code "117") (name "/SDIO_D0") (class "Default")
      (node (ref "U6") (pin "94") (pinfunction "PB14_94") (pintype "bidirectional"))
    )
    (net (code "118") (name "/SDIO_D1") (class "Default")
      (node (ref "U6") (pin "95") (pinfunction "PB15_95") (pintype "bidirectional"))
    )
    (net (code "119") (name "/SDIO_D2") (class "Default")
      (node (ref "U6") (pin "161") (pinfunction "PB3(JTDO/TRACESWO)_161") (pintype "bidirectional"))
    )
    (net (code "120") (name "/SDIO_D3") (class "Default")
      (node (ref "U6") (pin "162") (pinfunction "PB4(NJTRST)_162") (pintype "bidirectional"))
    )
    (net (code "122") (name "/SPI1_MISO") (class "Default")
      (node (ref "U6") (pin "52") (pinfunction "PA6_52") (pintype "bidirectional"))
    )
    (net (code "123") (name "/SPI1_MOSI") (class "Default")
      (node (ref "U6") (pin "53") (pinfunction "PA7_53") (pintype "bidirectional"))
    )
    (net (code "124") (name "/SPI1_NSS") (class "Default")
      (node (ref "U6") (pin "50") (pinfunction "PA4_50") (pintype "bidirectional"))
    )
    (net (code "125") (name "/SPI1_SCK") (class "Default")
      (node (ref "U6") (pin "51") (pinfunction "PA5_51") (pintype "bidirectional"))
    )
    (net (code "126") (name "/SWCLK") (class "Default")
      (node (ref "P2") (pin "3") (pinfunction "3_3") (pintype "passive"))
      (node (ref "U6") (pin "137") (pinfunction "PA14(JTCK-SWCLK)_137") (pintype "bidirectional"))
    )
    (net (code "127") (name "/SWDIO") (class "Default")
      (node (ref "P2") (pin "4") (pinfunction "4_4") (pintype "passive"))
      (node (ref "U6") (pin "124") (pinfunction "PA13(JTMS-SWDIO)_124") (pintype "bidirectional"))
    )
    (net (code "128") (name "/TIM_CH1") (class "Default")
      (node (ref "U6") (pin "56") (pinfunction "PB0_56") (pintype "bidirectional"))
    )
    (net (code "129") (name "/UART4_RX") (class "Default")
      (node (ref "U6") (pin "41") (pinfunction "PA1_41") (pintype "bidirectional"))
    )
    (net (code "130") (name "/UART4_TX") (class "Default")
      (node (ref "U6") (pin "40") (pinfunction "PA0-WKUP(PA0)_40") (pintype "bidirectional"))
    )
    (net (code "131") (name "/UART5_RX") (class "Default")
      (node (ref "U6") (pin "92") (pinfunction "PB12_92") (pintype "bidirectional"))
    )
    (net (code "132") (name "/UART5_TX") (class "Default")
      (node (ref "U6") (pin "93") (pinfunction "PB13_93") (pintype "bidirectional"))
    )
    (net (code "133") (name "/USART1_RX") (class "Default")
      (node (ref "U6") (pin "119") (pinfunction "PA8_119") (pintype "bidirectional"))
    )
    (net (code "134") (name "/USART1_TX") (class "Default")
      (node (ref "U6") (pin "120") (pinfunction "PA9_120") (pintype "bidirectional"))
    )
    (net (code "135") (name "/USART2_RX") (class "Default")
      (node (ref "U6") (pin "47") (pinfunction "PA3_47") (pintype "bidirectional"))
    )
    (net (code "136") (name "/USART2_TX") (class "Default")
      (node (ref "U6") (pin "42") (pinfunction "PA2_42") (pintype "bidirectional"))
    )
    (net (code "137") (name "/USART3_RX") (class "Default")
      (node (ref "U6") (pin "80") (pinfunction "PB11_80") (pintype "bidirectional"))
    )
    (net (code "138") (name "/USART3_TX") (class "Default")
      (node (ref "U6") (pin "139") (pinfunction "PC10_139") (pintype "bidirectional"))
    )
    (net (code "139") (name "/USBID") (class "Default")
      (node (ref "U6") (pin "121") (pinfunction "PA10_121") (pintype "bidirectional"))
    )
    (net (code "140") (name "/USB_DM") (class "Default")
      (node (ref "U6") (pin "122") (pinfunction "PA11_122") (pintype "bidirectional"))
    )
    (net (code "141") (name "/USB_DP") (class "Default")
      (node (ref "U6") (pin "123") (pinfunction "PA12_123") (pintype "bidirectional"))
    )
    (net (code "142") (name "/VDDA") (class "Default")
      (node (ref "C32") (pin "2") (pinfunction "2_2") (pintype "passive"))
      (node (ref "C33") (pin "2") (pinfunction "2_2") (pintype "passive"))
      (node (ref "L2") (pin "2") (pinfunction "2_2") (pintype "passive"))
      (node (ref "U6") (pin "38") (pinfunction "VREF+_38") (pintype "power_in"))
      (node (ref "U6") (pin "39") (pinfunction "VDDA_39") (pintype "power_in"))
    )
    (net (code "143") (name "/VSSA") (class "Default")
      (node (ref "C32") (pin "1") (pinfunction "1_1") (pintype "passive"))
      (node (ref "C33") (pin "1") (pinfunction "1_1") (pintype "passive"))
      (node (ref "L3") (pin "2") (pinfunction "2_2") (pintype "passive"))
      (node (ref "U6") (pin "37") (pinfunction "VSSA_37") (pintype "power_in"))
    )
    (net (code "144") (name "GND") (class "Default")
      (node (ref "BT1") (pin "2") (pinfunction "-_2") (pintype "passive"))
      (node (ref "C12") (pin "2") (pinfunction "2_2") (pintype "passive"))
      (node (ref "C13") (pin "1") (pinfunction "1_1") (pintype "passive"))
      (node (ref "C14") (pin "1") (pinfunction "1_1") (pintype "passive"))
      (node (ref "C15") (pin "1") (pinfunction "1_1") (pintype "passive"))
      (node (ref "C16") (pin "1") (pinfunction "1_1") (pintype "passive"))
      (node (ref "C17") (pin "1") (pinfunction "1_1") (pintype "passive"))
      (node (ref "C18") (pin "1") (pinfunction "1_1") (pintype "passive"))
      (node (ref "C19") (pin "1") (pinfunction "1_1") (pintype "passive"))
      (node (ref "C20") (pin "1") (pinfunction "1_1") (pintype "passive"))
      (node (ref "C21") (pin "1") (pinfunction "1_1") (pintype "passive"))
      (node (ref "C22") (pin "1") (pinfunction "1_1") (pintype "passive"))
      (node (ref "C23") (pin "1") (pinfunction "1_1") (pintype "passive"))
      (node (ref "C24") (pin "1") (pinfunction "1_1") (pintype "passive"))
      (node (ref "C25") (pin "1") (pinfunction "1_1") (pintype "passive"))
      (node (ref "C26") (pin "1") (pinfunction "1_1") (pintype "passive"))
      (node (ref "C27") (pin "1") (pinfunction "1_1") (pintype "passive"))
      (node (ref "C28") (pin "1") (pinfunction "1_1") (pintype "passive"))
      (node (ref "C29") (pin "1") (pinfunction "1_1") (pintype "passive"))
      (node (ref "C30") (pin "1") (pinfunction "1_1") (pintype "passive"))
      (node (ref "C31") (pin "1") (pinfunction "1_1") (pintype "passive"))
      (node (ref "C8") (pin "1") (pinfunction "1_1") (pintype "passive"))
      (node (ref "C9") (pin "2") (pinfunction "2_2") (pintype "passive"))
      (node (ref "L3") (pin "1") (pinfunction "1_1") (pintype "passive"))
      (node (ref "P2") (pin "1") (pinfunction "1_1") (pintype "passive"))
      (node (ref "R8") (pin "2") (pinfunction "2_2") (pintype "passive"))
      (node (ref "S1") (pin "1") (pinfunction "1_1") (pintype "passive"))
      (node (ref "U6") (pin "102") (pinfunction "VSS_102") (pintype "power_in"))
      (node (ref "U6") (pin "113") (pinfunction "VSS_113") (pintype "power_in"))
      (node (ref "U6") (pin "126") (pinfunction "VSS_126") (pintype "power_in"))
      (node (ref "U6") (pin "135") (pinfunction "VSS_135") (pintype "power_in"))
      (node (ref "U6") (pin "14") (pinfunction "VSS_14") (pintype "power_in"))
      (node (ref "U6") (pin "148") (pinfunction "VSS_148") (pintype "power_in"))
      (node (ref "U6") (pin "158") (pinfunction "VSS_158") (pintype "power_in"))
      (node (ref "U6") (pin "22") (pinfunction "VSS_22") (pintype "power_in"))
      (node (ref "U6") (pin "48") (pinfunction "BYPASS_REG_48") (pintype "input"))
      (node (ref "U6") (pin "61") (pinfunction "VSS_61") (pintype "power_in"))
      (node (ref "U6") (pin "71") (pinfunction "VSS_71") (pintype "power_in"))
      (node (ref "U6") (pin "90") (pinfunction "VSS_90") (pintype "power_in"))
    )
    (net (code "145") (name "Net-(BT1-+)") (class "Default")
      (node (ref "BT1") (pin "1") (pinfunction "+_1") (pintype "passive"))
      (node (ref "U6") (pin "6") (pinfunction "VBAT_6") (pintype "power_in"))
    )
    (net (code "146") (name "Net-(C8-Pad2)") (class "Default")
      (node (ref "C8") (pin "2") (pinfunction "2_2") (pintype "passive"))
      (node (ref "R4") (pin "2") (pinfunction "2_2") (pintype "passive"))
      (node (ref "Y1") (pin "2") (pinfunction "2_2") (pintype "passive"))
    )
    (net (code "147") (name "Net-(U6A-PC14-OSC32_IN(PC14))") (class "Default")
      (node (ref "C13") (pin "2") (pinfunction "2_2") (pintype "passive"))
      (node (ref "U6") (pin "9") (pinfunction "PC14-OSC32_IN(PC14)_9") (pintype "bidirectional"))
      (node (ref "Y2") (pin "1") (pinfunction "1_1") (pintype "passive"))
    )
    (net (code "148") (name "Net-(U6A-PC15-OSC32_OUT(PC15))") (class "Default")
      (node (ref "C16") (pin "2") (pinfunction "2_2") (pintype "passive"))
      (node (ref "U6") (pin "10") (pinfunction "PC15-OSC32_OUT(PC15)_10") (pintype "bidirectional"))
      (node (ref "Y2") (pin "2") (pinfunction "2_2") (pintype "passive"))
    )
    (net (code "149") (name "Net-(U6B-BOOT0)") (class "Default")
      (node (ref "JP1") (pin "1") (pinfunction "1_1") (pintype "passive"))
      (node (ref "R8") (pin "1") (pinfunction "1_1") (pintype "passive"))
      (node (ref "U6") (pin "166") (pinfunction "BOOT0_166") (pintype "input"))
    )
    (net (code "150") (name "Net-(U6B-PDR_ON)") (class "Default")
      (node (ref "R10") (pin "1") (pinfunction "1_1") (pintype "passive"))
      (node (ref "U6") (pin "171") (pinfunction "PDR_ON_171") (pintype "input"))
    )
    (net (code "151") (name "Net-(U6B-PH0-OSC_IN(PH0))") (class "Default")
      (node (ref "C9") (pin "1") (pinfunction "1_1") (pintype "passive"))
      (node (ref "U6") (pin "29") (pinfunction "PH0-OSC_IN(PH0)_29") (pintype "bidirectional"))
      (node (ref "Y1") (pin "1") (pinfunction "1_1") (pintype "passive"))
    )
    (net (code "152") (name "Net-(U6B-PH1-OSC_OUT(PH1))") (class "Default")
      (node (ref "R4") (pin "1") (pinfunction "1_1") (pintype "passive"))
      (node (ref "U6") (pin "30") (pinfunction "PH1-OSC_OUT(PH1)_30") (pintype "bidirectional"))
    )
    (net (code "153") (name "Net-(U6B-VCAP_1)") (class "Default")
      (node (ref "C15") (pin "2") (pinfunction "2_2") (pintype "passive"))
      (node (ref "U6") (pin "81") (pinfunction "VCAP_1_81") (pintype "power_in"))
    )
    (net (code "154") (name "Net-(U6B-VCAP_2)") (class "Default")
      (node (ref "C14") (pin "2") (pinfunction "2_2") (pintype "passive"))
      (node (ref "U6") (pin "125") (pinfunction "VCAP_2_125") (pintype "power_in"))
    )
    (net (code "155") (name "unconnected-(U6A-PC1-Pad33)") (class "Default")
      (node (ref "U6") (pin "33") (pinfunction "PC1_33") (pintype "bidirectional"))
    )
    (net (code "156") (name "unconnected-(U6A-PC9-Pad118)") (class "Default")
      (node (ref "U6") (pin "118") (pinfunction "PC9_118") (pintype "bidirectional"))
    )
    (net (code "157") (name "unconnected-(U6A-PC12-Pad141)") (class "Default")
      (node (ref "U6") (pin "141") (pinfunction "PC12_141") (pintype "bidirectional"))
    )
    (net (code "158") (name "unconnected-(U6B-PG12-Pad155)") (class "Default")
      (node (ref "U6") (pin "155") (pinfunction "PG12_155") (pintype "bidirectional"))
    )
    (net (code "159") (name "unconnected-(U6B-PG13-Pad156)") (class "Default")
      (node (ref "U6") (pin "156") (pinfunction "PG13_156") (pintype "bidirectional"))
    )
  )
)
